# graviton.net
KiCad netlist of a schematic drawn in Altium Designer
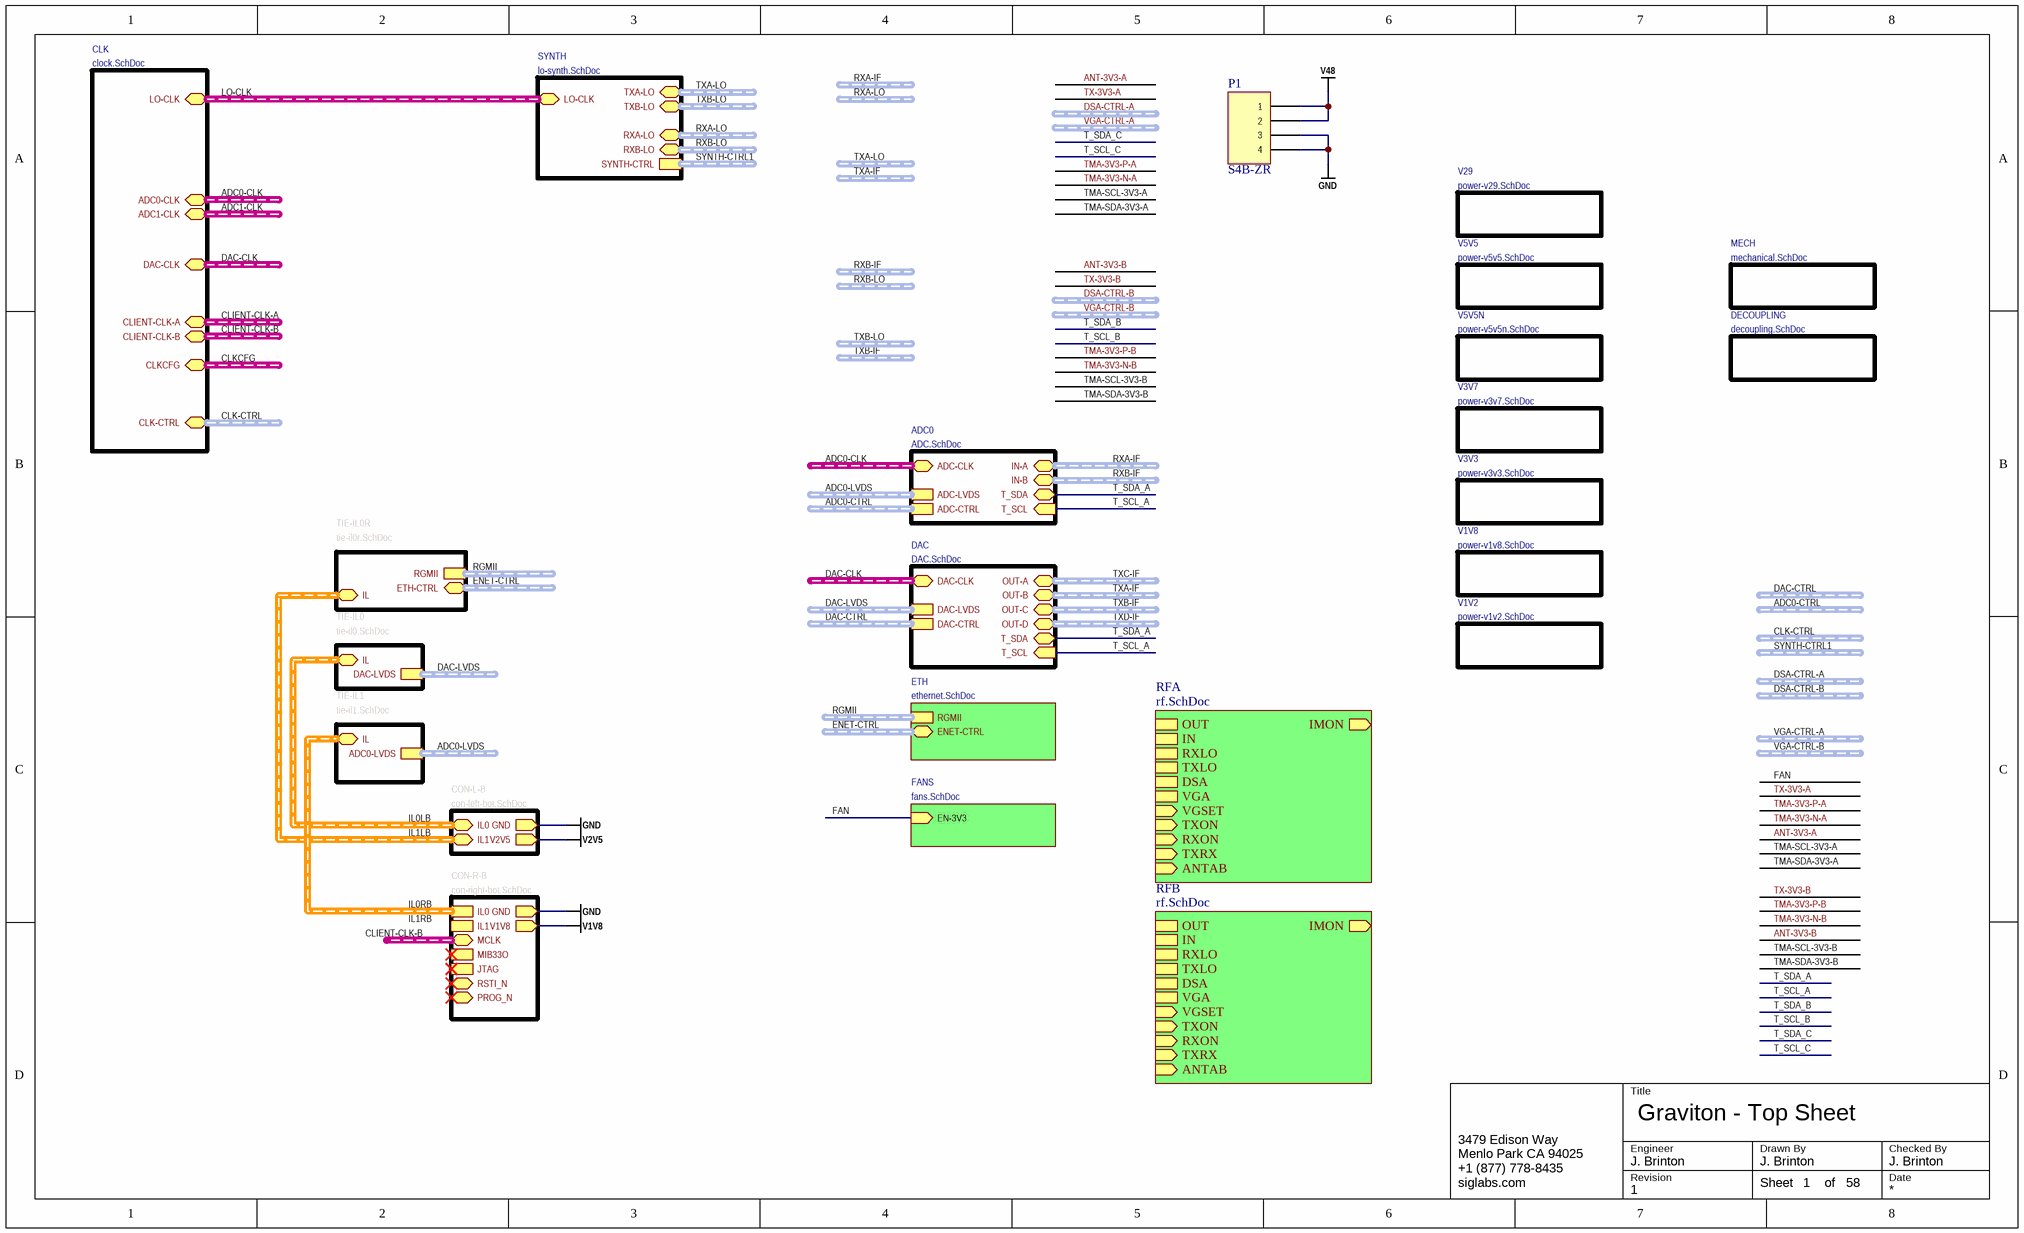
[diagram p0: graviton.SchDoc]

(export (version "E")
  (design (tool "Eeschema 10.0.6"))
  (components
    (comp (ref "P1")
      (value "S4B-ZR")
      (footprint "jst:S4B-ZR")
      (description "1.5mm pitch right angle 6-position")
      (fields (field (name "MANUFACTURER") "JST"))
      (libsource (lib "jst") (part "S4B-ZR"))
    )
  )
  (nets
    (net (code "115") (name "GND") (class "Default")
      (node (ref "P1") (pin "3") (pinfunction "3_3") (pintype "passive"))
      (node (ref "P1") (pin "4") (pinfunction "4_4") (pintype "passive"))
    )
    (net (code "118") (name "V48") (class "Default")
      (node (ref "P1") (pin "1") (pinfunction "1_1") (pintype "passive"))
      (node (ref "P1") (pin "2") (pinfunction "2_2") (pintype "passive"))
    )
  )
)
